# openLRSngTX.net
KiCad netlist of a schematic drawn in EAGLE
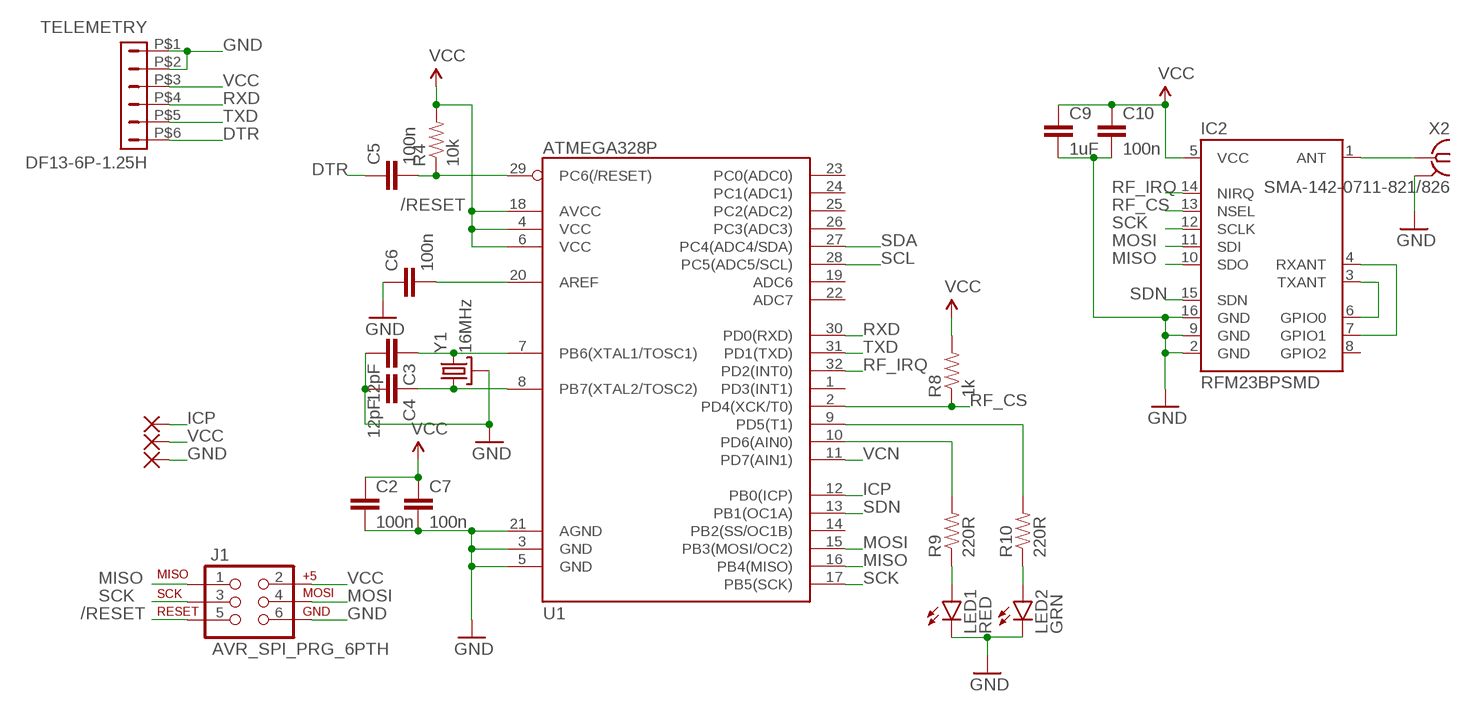
[diagram p0: schematic, sheet 1]

(export (version "E")
  (design (tool "Eeschema 10.0.6"))
  (components
    (comp (ref "C2")
      (value "100n")
      (footprint "eagle-import:0805")
      (libsource (lib "eagle-import") (part "CAP0805"))
    )
    (comp (ref "C3")
      (value "12pF")
      (footprint "eagle-import:0805")
      (libsource (lib "eagle-import") (part "CAP0805"))
    )
    (comp (ref "C4")
      (value "12pF")
      (footprint "eagle-import:0805")
      (libsource (lib "eagle-import") (part "CAP0805"))
    )
    (comp (ref "C5")
      (value "100n")
      (footprint "eagle-import:0805")
      (libsource (lib "eagle-import") (part "CAP0805"))
    )
    (comp (ref "C6")
      (value "100n")
      (footprint "eagle-import:0805")
      (libsource (lib "eagle-import") (part "CAP0805"))
    )
    (comp (ref "C7")
      (value "100n")
      (footprint "eagle-import:0805")
      (libsource (lib "eagle-import") (part "CAP0805"))
    )
    (comp (ref "C9")
      (value "1uF")
      (footprint "eagle-import:0805")
      (libsource (lib "eagle-import") (part "CAP0805"))
    )
    (comp (ref "C10")
      (value "100n")
      (footprint "eagle-import:0805")
      (libsource (lib "eagle-import") (part "CAP0805"))
    )
    (comp (ref "GND")
      (value "WIREPADSMD1,27-254")
      (footprint "eagle-import:SMD1,27-2,54")
      (libsource (lib "eagle-import") (part "WIREPADSMD1,27-254"))
    )
    (comp (ref "IC2")
      (value "RFM23BPSMD")
      (footprint "eagle-import:RFM23BP-S2")
      (libsource (lib "eagle-import") (part "RFM23BPSMD"))
    )
    (comp (ref "ICP")
      (value "WIREPADSMD1,27-254")
      (footprint "eagle-import:SMD1,27-2,54")
      (libsource (lib "eagle-import") (part "WIREPADSMD1,27-254"))
    )
    (comp (ref "J1")
      (value "AVR_SPI_PRG_6PTH")
      (footprint "eagle-import:2X3")
      (libsource (lib "eagle-import") (part "AVR_SPI_PRG_6PTH"))
    )
    (comp (ref "LED1")
      (value "RED")
      (footprint "eagle-import:LED-1206")
      (libsource (lib "eagle-import") (part "LED1206"))
    )
    (comp (ref "LED2")
      (value "GRN")
      (footprint "eagle-import:LED-1206")
      (libsource (lib "eagle-import") (part "LED1206"))
    )
    (comp (ref "R4")
      (value "10k")
      (footprint "eagle-import:0805")
      (libsource (lib "eagle-import") (part "RESISTOR0805-RES"))
    )
    (comp (ref "R8")
      (value "1k")
      (footprint "eagle-import:0805")
      (libsource (lib "eagle-import") (part "RESISTOR0805-RES"))
    )
    (comp (ref "R9")
      (value "220R")
      (footprint "eagle-import:0805")
      (libsource (lib "eagle-import") (part "RESISTOR0805-RES"))
    )
    (comp (ref "R10")
      (value "220R")
      (footprint "eagle-import:0805")
      (libsource (lib "eagle-import") (part "RESISTOR0805-RES"))
    )
    (comp (ref "TELEMETRY")
      (value "DF13-6P-1.25H")
      (footprint "eagle-import:DF13A-6P-1.25H")
      (libsource (lib "eagle-import") (part "DF13-6P-1.25H"))
    )
    (comp (ref "U1")
      (value "ATMEGA328P")
      (footprint "eagle-import:TQFP32-08")
      (libsource (lib "eagle-import") (part "ATMEGA328_SMT"))
    )
    (comp (ref "VCC")
      (value "WIREPADSMD1,27-254")
      (footprint "eagle-import:SMD1,27-2,54")
      (libsource (lib "eagle-import") (part "WIREPADSMD1,27-254"))
    )
    (comp (ref "X2")
      (value "SMA-142-0711-821/826")
      (footprint "eagle-import:J502-ND-142-0711-821_826")
      (fields (field (name "MF") "JOHNSON COMPONENTS") (field (name "MPN") "142-0711-821"))
      (libsource (lib "eagle-import") (part "SMA-142-0711-821/826"))
    )
    (comp (ref "Y1")
      (value "16MHz")
      (footprint "eagle-import:CRYSTAL-SMD-5X3")
      (libsource (lib "eagle-import") (part "CRYSTAL3.2X2.5"))
    )
  )
  (nets
    (net (code "1") (name "/DTR") (class "Default")
      (node (ref "C5") (pin "1") (pinfunction "1_1") (pintype "passive"))
      (node (ref "TELEMETRY") (pin "P$6") (pinfunction "6_P$6") (pintype "passive"))
    )
    (net (code "2") (name "/ICP") (class "Default")
      (node (ref "ICP") (pin "1") (pinfunction "P_1") (pintype "passive"))
      (node (ref "U1") (pin "12") (pinfunction "PB0(ICP)_12") (pintype "bidirectional"))
    )
    (net (code "3") (name "/MISO") (class "Default")
      (node (ref "IC2") (pin "10") (pinfunction "SDO_10") (pintype "output"))
      (node (ref "J1") (pin "1") (pinfunction "1_1") (pintype "passive"))
      (node (ref "U1") (pin "16") (pinfunction "PB4(MISO)_16") (pintype "bidirectional"))
    )
    (net (code "4") (name "/MOSI") (class "Default")
      (node (ref "IC2") (pin "11") (pinfunction "SDI_11") (pintype "input"))
      (node (ref "J1") (pin "4") (pinfunction "4_4") (pintype "passive"))
      (node (ref "U1") (pin "15") (pinfunction "PB3(MOSI/OC2)_15") (pintype "bidirectional"))
    )
    (net (code "5") (name "/RF_CS") (class "Default")
      (node (ref "IC2") (pin "13") (pinfunction "NSEL_13") (pintype "input"))
      (node (ref "R8") (pin "1") (pinfunction "1_1") (pintype "passive"))
      (node (ref "U1") (pin "2") (pinfunction "PD4(XCK/T0)_2") (pintype "bidirectional"))
    )
    (net (code "6") (name "/RF_IRQ") (class "Default")
      (node (ref "IC2") (pin "14") (pinfunction "NIRQ_14") (pintype "output"))
      (node (ref "U1") (pin "32") (pinfunction "PD2(INT0)_32") (pintype "bidirectional"))
    )
    (net (code "7") (name "/RXD") (class "Default")
      (node (ref "TELEMETRY") (pin "P$4") (pinfunction "4_P$4") (pintype "passive"))
      (node (ref "U1") (pin "30") (pinfunction "PD0(RXD)_30") (pintype "bidirectional"))
    )
    (net (code "8") (name "/SCK") (class "Default")
      (node (ref "IC2") (pin "12") (pinfunction "SCLK_12") (pintype "input"))
      (node (ref "J1") (pin "3") (pinfunction "3_3") (pintype "passive"))
      (node (ref "U1") (pin "17") (pinfunction "PB5(SCK)_17") (pintype "bidirectional"))
    )
    (net (code "9") (name "/SCL") (class "Default")
      (node (ref "U1") (pin "28") (pinfunction "PC5(ADC5/SCL)_28") (pintype "bidirectional"))
    )
    (net (code "10") (name "/SDA") (class "Default")
      (node (ref "U1") (pin "27") (pinfunction "PC4(ADC4/SDA)_27") (pintype "bidirectional"))
    )
    (net (code "11") (name "/SDN") (class "Default")
      (node (ref "IC2") (pin "15") (pinfunction "SDN_15") (pintype "input"))
      (node (ref "U1") (pin "13") (pinfunction "PB1(OC1A)_13") (pintype "bidirectional"))
    )
    (net (code "12") (name "/TXD") (class "Default")
      (node (ref "TELEMETRY") (pin "P$5") (pinfunction "5_P$5") (pintype "passive"))
      (node (ref "U1") (pin "31") (pinfunction "PD1(TXD)_31") (pintype "bidirectional"))
    )
    (net (code "13") (name "/VCN") (class "Default")
      (node (ref "U1") (pin "11") (pinfunction "PD7(AIN1)_11") (pintype "bidirectional"))
    )
    (net (code "14") (name "/{slash}RESET") (class "Default")
      (node (ref "C5") (pin "2") (pinfunction "2_2") (pintype "passive"))
      (node (ref "J1") (pin "5") (pinfunction "5_5") (pintype "passive"))
      (node (ref "R4") (pin "1") (pinfunction "1_1") (pintype "passive"))
      (node (ref "U1") (pin "29") (pinfunction "PC6(/RESET)_29") (pintype "bidirectional"))
    )
    (net (code "15") (name "GND") (class "Default")
      (node (ref "C10") (pin "2") (pinfunction "2_2") (pintype "passive"))
      (node (ref "C2") (pin "2") (pinfunction "2_2") (pintype "passive"))
      (node (ref "C3") (pin "2") (pinfunction "2_2") (pintype "passive"))
      (node (ref "C4") (pin "2") (pinfunction "2_2") (pintype "passive"))
      (node (ref "C6") (pin "1") (pinfunction "1_1") (pintype "passive"))
      (node (ref "C7") (pin "2") (pinfunction "2_2") (pintype "passive"))
      (node (ref "C9") (pin "2") (pinfunction "2_2") (pintype "passive"))
      (node (ref "GND") (pin "1") (pinfunction "P_1") (pintype "passive"))
      (node (ref "IC2") (pin "16") (pinfunction "GND_16") (pintype "power_in"))
      (node (ref "IC2") (pin "2") (pinfunction "GND_2") (pintype "power_in"))
      (node (ref "IC2") (pin "9") (pinfunction "GND_9") (pintype "power_in"))
      (node (ref "J1") (pin "6") (pinfunction "6_6") (pintype "passive"))
      (node (ref "LED1") (pin "C") (pinfunction "C_C") (pintype "passive"))
      (node (ref "LED2") (pin "C") (pinfunction "C_C") (pintype "passive"))
      (node (ref "TELEMETRY") (pin "P$1") (pinfunction "1_P$1") (pintype "passive"))
      (node (ref "TELEMETRY") (pin "P$2") (pinfunction "2_P$2") (pintype "passive"))
      (node (ref "U1") (pin "21") (pinfunction "AGND_21") (pintype "bidirectional"))
      (node (ref "U1") (pin "3") (pinfunction "GND_3") (pintype "bidirectional"))
      (node (ref "U1") (pin "5") (pinfunction "GND_5") (pintype "bidirectional"))
      (node (ref "X2") (pin "G@1") (pinfunction "2_G@1") (pintype "passive"))
      (node (ref "X2") (pin "G@2") (pinfunction "2_G@2") (pintype "passive"))
      (node (ref "X2") (pin "G@3") (pinfunction "2_G@3") (pintype "passive"))
      (node (ref "X2") (pin "G@4") (pinfunction "2_G@4") (pintype "passive"))
      (node (ref "Y1") (pin "2") (pinfunction "GND_2") (pintype "power_in"))
      (node (ref "Y1") (pin "4") (pinfunction "GND_4") (pintype "power_in"))
    )
    (net (code "16") (name "Net-(IC2-ANT)") (class "Default")
      (node (ref "IC2") (pin "1") (pinfunction "ANT_1") (pintype "bidirectional"))
      (node (ref "X2") (pin "1") (pinfunction "1_1") (pintype "passive"))
    )
    (net (code "17") (name "Net-(IC2-GPIO0)") (class "Default")
      (node (ref "IC2") (pin "3") (pinfunction "TXANT_3") (pintype "input"))
      (node (ref "IC2") (pin "6") (pinfunction "GPIO0_6") (pintype "bidirectional"))
    )
    (net (code "18") (name "Net-(IC2-GPIO1)") (class "Default")
      (node (ref "IC2") (pin "4") (pinfunction "RXANT_4") (pintype "input"))
      (node (ref "IC2") (pin "7") (pinfunction "GPIO1_7") (pintype "bidirectional"))
    )
    (net (code "19") (name "Net-(LED1-PadA)") (class "Default")
      (node (ref "LED1") (pin "A") (pinfunction "A_A") (pintype "passive"))
      (node (ref "R9") (pin "1") (pinfunction "1_1") (pintype "passive"))
    )
    (net (code "20") (name "Net-(LED2-PadA)") (class "Default")
      (node (ref "LED2") (pin "A") (pinfunction "A_A") (pintype "passive"))
      (node (ref "R10") (pin "1") (pinfunction "1_1") (pintype "passive"))
    )
    (net (code "21") (name "Net-(U1-AREF)") (class "Default")
      (node (ref "C6") (pin "2") (pinfunction "2_2") (pintype "passive"))
      (node (ref "U1") (pin "20") (pinfunction "AREF_20") (pintype "bidirectional"))
    )
    (net (code "22") (name "Net-(U1-PB6(XTAL1{slash}TOSC1))") (class "Default")
      (node (ref "C3") (pin "1") (pinfunction "1_1") (pintype "passive"))
      (node (ref "U1") (pin "7") (pinfunction "PB6(XTAL1/TOSC1)_7") (pintype "bidirectional"))
      (node (ref "Y1") (pin "3") (pinfunction "2_3") (pintype "passive"))
    )
    (net (code "23") (name "Net-(U1-PB7(XTAL2{slash}TOSC2))") (class "Default")
      (node (ref "C4") (pin "1") (pinfunction "1_1") (pintype "passive"))
      (node (ref "U1") (pin "8") (pinfunction "PB7(XTAL2/TOSC2)_8") (pintype "bidirectional"))
      (node (ref "Y1") (pin "1") (pinfunction "1_1") (pintype "passive"))
    )
    (net (code "24") (name "Net-(U1-PD5(T1))") (class "Default")
      (node (ref "R10") (pin "2") (pinfunction "2_2") (pintype "passive"))
      (node (ref "U1") (pin "9") (pinfunction "PD5(T1)_9") (pintype "bidirectional"))
    )
    (net (code "25") (name "Net-(U1-PD6(AIN0))") (class "Default")
      (node (ref "R9") (pin "2") (pinfunction "2_2") (pintype "passive"))
      (node (ref "U1") (pin "10") (pinfunction "PD6(AIN0)_10") (pintype "bidirectional"))
    )
    (net (code "26") (name "VCC") (class "Default")
      (node (ref "C10") (pin "1") (pinfunction "1_1") (pintype "passive"))
      (node (ref "C2") (pin "1") (pinfunction "1_1") (pintype "passive"))
      (node (ref "C7") (pin "1") (pinfunction "1_1") (pintype "passive"))
      (node (ref "C9") (pin "1") (pinfunction "1_1") (pintype "passive"))
      (node (ref "IC2") (pin "5") (pinfunction "VCC_5") (pintype "bidirectional"))
      (node (ref "J1") (pin "2") (pinfunction "2_2") (pintype "passive"))
      (node (ref "R4") (pin "2") (pinfunction "2_2") (pintype "passive"))
      (node (ref "R8") (pin "2") (pinfunction "2_2") (pintype "passive"))
      (node (ref "TELEMETRY") (pin "P$3") (pinfunction "3_P$3") (pintype "passive"))
      (node (ref "U1") (pin "18") (pinfunction "AVCC_18") (pintype "bidirectional"))
      (node (ref "U1") (pin "4") (pinfunction "VCC_4") (pintype "bidirectional"))
      (node (ref "U1") (pin "6") (pinfunction "VCC_6") (pintype "bidirectional"))
      (node (ref "VCC") (pin "1") (pinfunction "P_1") (pintype "passive"))
    )
    (net (code "27") (name "unconnected-(IC2-GPIO2-Pad8)") (class "Default")
      (node (ref "IC2") (pin "8") (pinfunction "GPIO2_8") (pintype "bidirectional"))
    )
    (net (code "28") (name "unconnected-(U1-ADC6-Pad19)") (class "Default")
      (node (ref "U1") (pin "19") (pinfunction "ADC6_19") (pintype "bidirectional"))
    )
    (net (code "29") (name "unconnected-(U1-ADC7-Pad22)") (class "Default")
      (node (ref "U1") (pin "22") (pinfunction "ADC7_22") (pintype "bidirectional"))
    )
    (net (code "30") (name "unconnected-(U1-PB2(SS{slash}OC1B)-Pad14)") (class "Default")
      (node (ref "U1") (pin "14") (pinfunction "PB2(SS/OC1B)_14") (pintype "bidirectional"))
    )
    (net (code "31") (name "unconnected-(U1-PC0(ADC0)-Pad23)") (class "Default")
      (node (ref "U1") (pin "23") (pinfunction "PC0(ADC0)_23") (pintype "bidirectional"))
    )
    (net (code "32") (name "unconnected-(U1-PC1(ADC1)-Pad24)") (class "Default")
      (node (ref "U1") (pin "24") (pinfunction "PC1(ADC1)_24") (pintype "bidirectional"))
    )
    (net (code "33") (name "unconnected-(U1-PC2(ADC2)-Pad25)") (class "Default")
      (node (ref "U1") (pin "25") (pinfunction "PC2(ADC2)_25") (pintype "bidirectional"))
    )
    (net (code "34") (name "unconnected-(U1-PC3(ADC3)-Pad26)") (class "Default")
      (node (ref "U1") (pin "26") (pinfunction "PC3(ADC3)_26") (pintype "bidirectional"))
    )
    (net (code "35") (name "unconnected-(U1-PD3(INT1)-Pad1)") (class "Default")
      (node (ref "U1") (pin "1") (pinfunction "PD3(INT1)_1") (pintype "bidirectional"))
    )
  )
)
